# USB2Serial_CH340G_v1_0.net
KiCad netlist of a schematic drawn in EAGLE
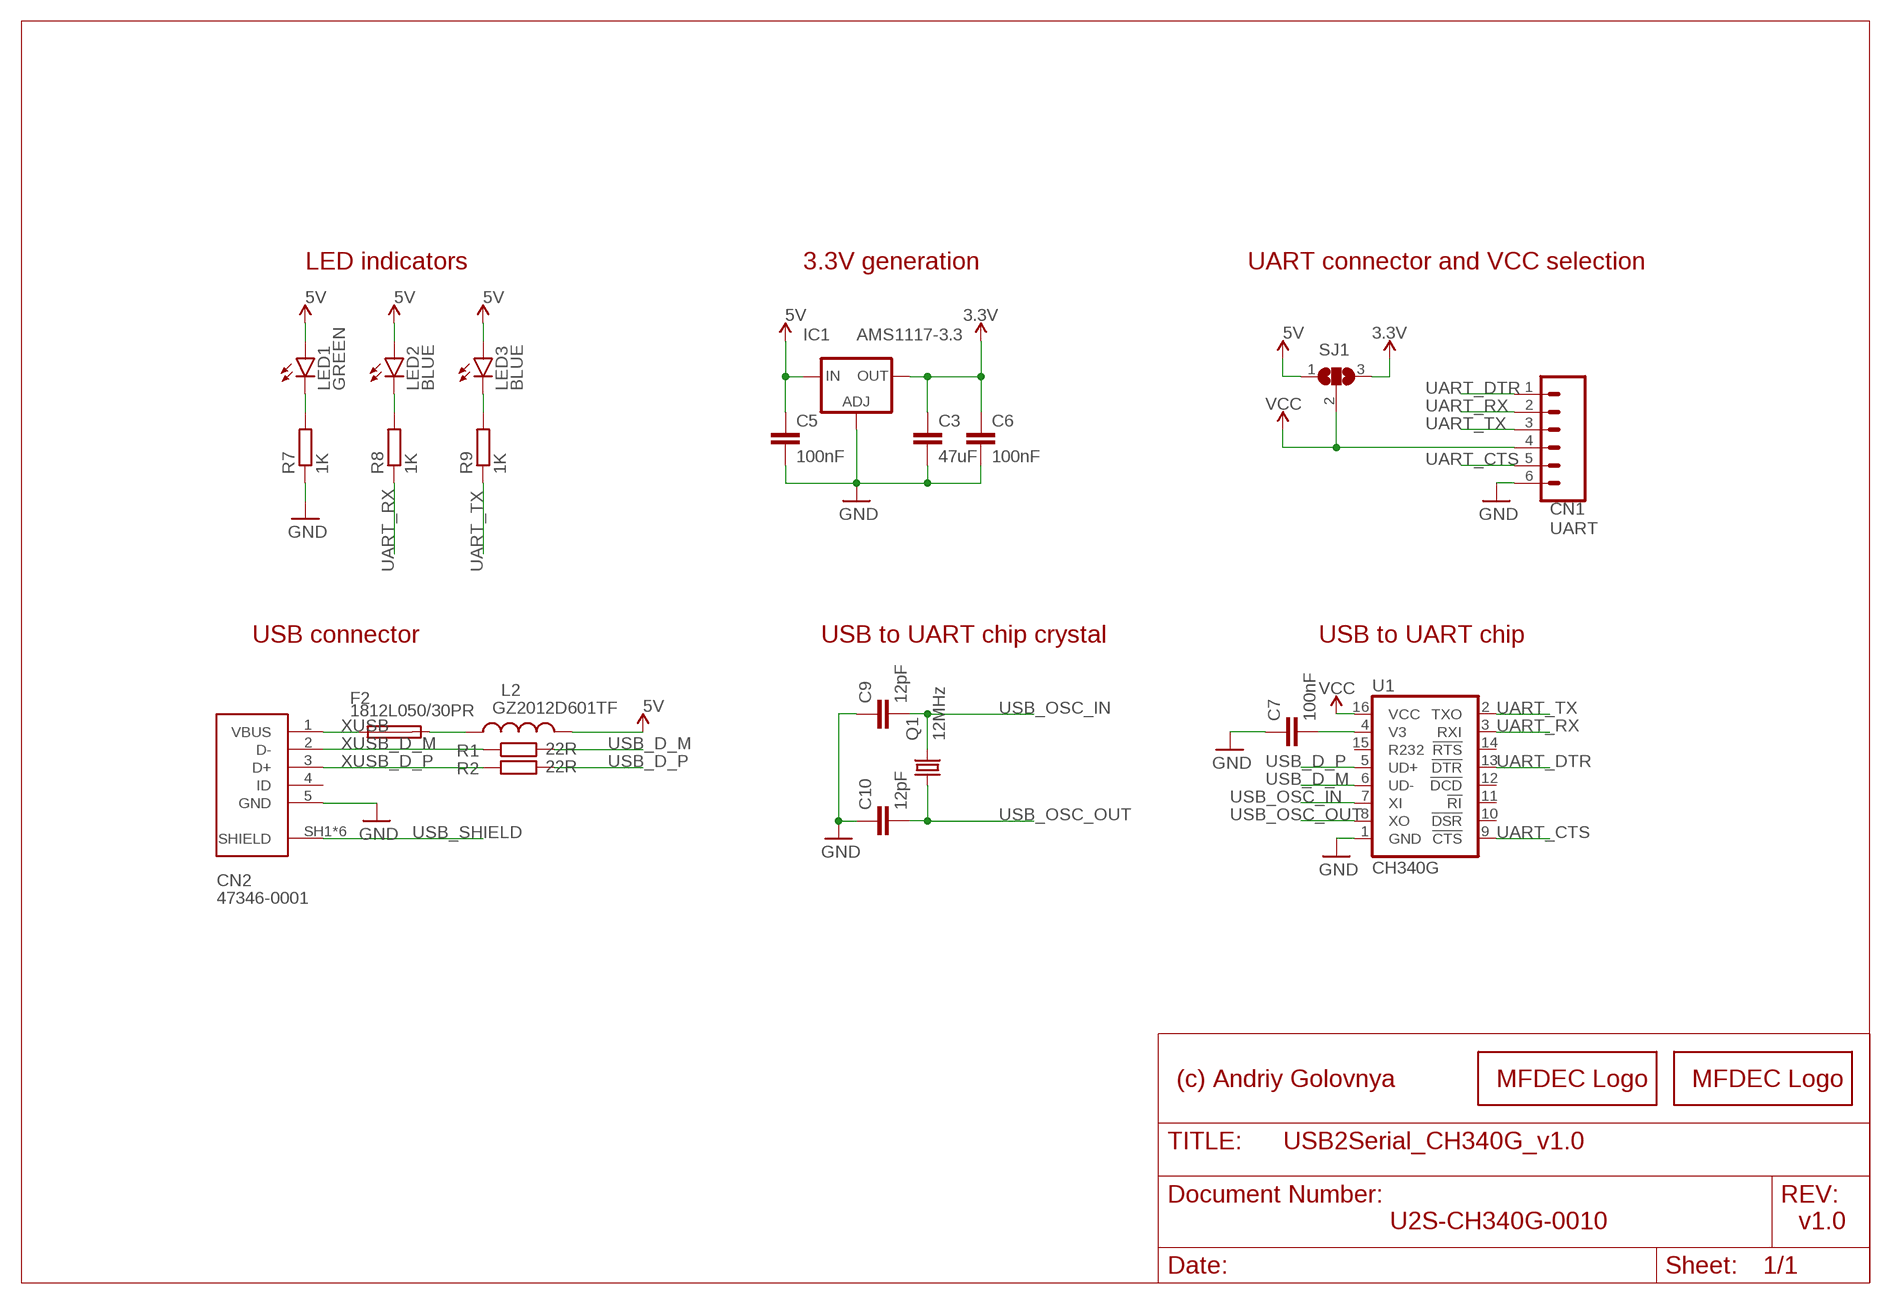
[diagram p0: schematic, sheet 1]

(export (version "E")
  (design (tool "Eeschema 10.0.6"))
  (components
    (comp (ref "C3")
      (value "47uF")
      (footprint "eagle-import:C0805")
      (libsource (lib "eagle-import") (part "C-EUC0805"))
    )
    (comp (ref "C5")
      (value "100nF")
      (footprint "eagle-import:C0402")
      (libsource (lib "eagle-import") (part "C-EUC0402"))
    )
    (comp (ref "C6")
      (value "100nF")
      (footprint "eagle-import:C0402")
      (libsource (lib "eagle-import") (part "C-EUC0402"))
    )
    (comp (ref "C7")
      (value "100nF")
      (footprint "eagle-import:C0402")
      (libsource (lib "eagle-import") (part "C-EUC0402"))
    )
    (comp (ref "C9")
      (value "12pF")
      (footprint "eagle-import:C0402")
      (libsource (lib "eagle-import") (part "C-EUC0402"))
    )
    (comp (ref "C10")
      (value "12pF")
      (footprint "eagle-import:C0402")
      (libsource (lib "eagle-import") (part "C-EUC0402"))
    )
    (comp (ref "CN1")
      (value "UART")
      (footprint "eagle-import:1X06_NO_SILK")
      (libsource (lib "eagle-import") (part "CONN_06NO_SILK_FEMALE_PTH"))
    )
    (comp (ref "CN2")
      (value "47346-0001")
      (footprint "eagle-import:MOLEX_47346-0001")
      (fields (field (name "MANUFACTURER") "Molex"))
      (libsource (lib "eagle-import") (part "47346-0001"))
    )
    (comp (ref "F2")
      (value "1812L050/30PR")
      (footprint "eagle-import:MF-SMDF050")
      (libsource (lib "eagle-import") (part "MF-SMDF050"))
    )
    (comp (ref "IC1")
      (value "AMS1117-3.3")
      (footprint "eagle-import:SOT223")
      (libsource (lib "eagle-import") (part "LD117A?S33TR"))
    )
    (comp (ref "L2")
      (value "GZ2012D601TF")
      (footprint "eagle-import:WE-CBA_0805(W=4)")
      (libsource (lib "eagle-import") (part "WE-CBA_0805_HC_782853102"))
    )
    (comp (ref "LED1")
      (value "GREEN")
      (footprint "eagle-import:SML0603")
      (libsource (lib "eagle-import") (part "LEDSML0603"))
    )
    (comp (ref "LED2")
      (value "BLUE")
      (footprint "eagle-import:SML0603")
      (libsource (lib "eagle-import") (part "LEDSML0603"))
    )
    (comp (ref "LED3")
      (value "BLUE")
      (footprint "eagle-import:SML0603")
      (libsource (lib "eagle-import") (part "LEDSML0603"))
    )
    (comp (ref "LOGO1")
      (value "MFDECLOGO_L_20MM")
      (footprint "eagle-import:MFDEC_L_20MM")
      (libsource (lib "eagle-import") (part "MFDECLOGO_L_20MM"))
    )
    (comp (ref "LOGO2")
      (value "MFDECLOGO_SQ_10MM")
      (footprint "eagle-import:MFDEC_SQ_10MM")
      (libsource (lib "eagle-import") (part "MFDECLOGO_SQ_10MM"))
    )
    (comp (ref "Q1")
      (value "12MHz")
      (footprint "eagle-import:3.2X2.5_KX-7")
      (libsource (lib "eagle-import") (part "KX-7"))
    )
    (comp (ref "R1")
      (value "22R")
      (footprint "eagle-import:R0402")
      (libsource (lib "eagle-import") (part "R-EU_R0402"))
    )
    (comp (ref "R2")
      (value "22R")
      (footprint "eagle-import:R0402")
      (libsource (lib "eagle-import") (part "R-EU_R0402"))
    )
    (comp (ref "R7")
      (value "1K")
      (footprint "eagle-import:R0402")
      (libsource (lib "eagle-import") (part "R-EU_R0402"))
    )
    (comp (ref "R8")
      (value "1K")
      (footprint "eagle-import:R0402")
      (libsource (lib "eagle-import") (part "R-EU_R0402"))
    )
    (comp (ref "R9")
      (value "1K")
      (footprint "eagle-import:R0402")
      (libsource (lib "eagle-import") (part "R-EU_R0402"))
    )
    (comp (ref "SJ1")
      (value "SJ2FI")
      (footprint "eagle-import:SJ_2FI")
      (libsource (lib "eagle-import") (part "SJ2FI"))
    )
    (comp (ref "U1")
      (value "CH340G")
      (footprint "eagle-import:SO016")
      (libsource (lib "eagle-import") (part "CH340GSMD"))
    )
  )
  (nets
    (net (code "1") (name "/UART_CTS") (class "Default")
      (node (ref "CN1") (pin "5") (pinfunction "5_5") (pintype "passive"))
      (node (ref "U1") (pin "9") (pinfunction "~{CTS}_9") (pintype "bidirectional"))
    )
    (net (code "2") (name "/UART_DTR") (class "Default")
      (node (ref "CN1") (pin "1") (pinfunction "1_1") (pintype "passive"))
      (node (ref "U1") (pin "13") (pinfunction "~{DTR}_13") (pintype "bidirectional"))
    )
    (net (code "3") (name "/UART_RX") (class "Default")
      (node (ref "CN1") (pin "2") (pinfunction "2_2") (pintype "passive"))
      (node (ref "R8") (pin "1") (pinfunction "1_1") (pintype "passive"))
      (node (ref "U1") (pin "3") (pinfunction "RXI_3") (pintype "bidirectional"))
    )
    (net (code "4") (name "/UART_TX") (class "Default")
      (node (ref "CN1") (pin "3") (pinfunction "3_3") (pintype "passive"))
      (node (ref "R9") (pin "1") (pinfunction "1_1") (pintype "passive"))
      (node (ref "U1") (pin "2") (pinfunction "TXO_2") (pintype "bidirectional"))
    )
    (net (code "5") (name "/USB_D_M") (class "Default")
      (node (ref "R1") (pin "2") (pinfunction "2_2") (pintype "passive"))
      (node (ref "U1") (pin "6") (pinfunction "UD-_6") (pintype "bidirectional"))
    )
    (net (code "6") (name "/USB_D_P") (class "Default")
      (node (ref "R2") (pin "2") (pinfunction "2_2") (pintype "passive"))
      (node (ref "U1") (pin "5") (pinfunction "UD+_5") (pintype "bidirectional"))
    )
    (net (code "7") (name "/USB_OSC_IN") (class "Default")
      (node (ref "C9") (pin "2") (pinfunction "2_2") (pintype "passive"))
      (node (ref "Q1") (pin "3") (pinfunction "2_3") (pintype "passive"))
      (node (ref "U1") (pin "7") (pinfunction "XI_7") (pintype "bidirectional"))
    )
    (net (code "8") (name "/USB_OSC_OUT") (class "Default")
      (node (ref "C10") (pin "2") (pinfunction "2_2") (pintype "passive"))
      (node (ref "Q1") (pin "1") (pinfunction "1_1") (pintype "passive"))
      (node (ref "U1") (pin "8") (pinfunction "XO_8") (pintype "bidirectional"))
    )
    (net (code "9") (name "/USB_SHIELD") (class "Default")
      (node (ref "CN2") (pin "SH1") (pinfunction "SHIELD_SH1") (pintype "passive"))
      (node (ref "CN2") (pin "SH2") (pinfunction "SHIELD_SH2") (pintype "passive"))
      (node (ref "CN2") (pin "SH3") (pinfunction "SHIELD_SH3") (pintype "passive"))
      (node (ref "CN2") (pin "SH4") (pinfunction "SHIELD_SH4") (pintype "passive"))
      (node (ref "CN2") (pin "SH5") (pinfunction "SHIELD_SH5") (pintype "passive"))
      (node (ref "CN2") (pin "SH6") (pinfunction "SHIELD_SH6") (pintype "passive"))
    )
    (net (code "10") (name "/XUSB") (class "Default")
      (node (ref "CN2") (pin "1") (pinfunction "VBUS_1") (pintype "power_in"))
      (node (ref "F2") (pin "1") (pinfunction "1_1") (pintype "passive"))
    )
    (net (code "11") (name "/XUSB_D_M") (class "Default")
      (node (ref "CN2") (pin "2") (pinfunction "D-_2") (pintype "bidirectional"))
      (node (ref "R1") (pin "1") (pinfunction "1_1") (pintype "passive"))
    )
    (net (code "12") (name "/XUSB_D_P") (class "Default")
      (node (ref "CN2") (pin "3") (pinfunction "D+_3") (pintype "bidirectional"))
      (node (ref "R2") (pin "1") (pinfunction "1_1") (pintype "passive"))
    )
    (net (code "13") (name "3.3V") (class "Default")
      (node (ref "C3") (pin "1") (pinfunction "1_1") (pintype "passive"))
      (node (ref "C6") (pin "1") (pinfunction "1_1") (pintype "passive"))
      (node (ref "IC1") (pin "4") (pinfunction "OUT_4") (pintype "passive"))
      (node (ref "SJ1") (pin "3") (pinfunction "3_3") (pintype "passive"))
    )
    (net (code "14") (name "5V") (class "Default")
      (node (ref "C5") (pin "1") (pinfunction "1_1") (pintype "passive"))
      (node (ref "IC1") (pin "3") (pinfunction "IN_3") (pintype "input"))
      (node (ref "L2") (pin "2") (pinfunction "2_2") (pintype "passive"))
      (node (ref "LED1") (pin "A") (pinfunction "A_A") (pintype "passive"))
      (node (ref "LED2") (pin "A") (pinfunction "A_A") (pintype "passive"))
      (node (ref "LED3") (pin "A") (pinfunction "A_A") (pintype "passive"))
      (node (ref "SJ1") (pin "1") (pinfunction "1_1") (pintype "passive"))
    )
    (net (code "15") (name "GND") (class "Default")
      (node (ref "C10") (pin "1") (pinfunction "1_1") (pintype "passive"))
      (node (ref "C3") (pin "2") (pinfunction "2_2") (pintype "passive"))
      (node (ref "C5") (pin "2") (pinfunction "2_2") (pintype "passive"))
      (node (ref "C6") (pin "2") (pinfunction "2_2") (pintype "passive"))
      (node (ref "C7") (pin "1") (pinfunction "1_1") (pintype "passive"))
      (node (ref "C9") (pin "1") (pinfunction "1_1") (pintype "passive"))
      (node (ref "CN1") (pin "6") (pinfunction "6_6") (pintype "passive"))
      (node (ref "CN2") (pin "5") (pinfunction "GND_5") (pintype "power_in"))
      (node (ref "IC1") (pin "1") (pinfunction "ADJ_1") (pintype "input"))
      (node (ref "R7") (pin "1") (pinfunction "1_1") (pintype "passive"))
      (node (ref "U1") (pin "1") (pinfunction "GND_1") (pintype "bidirectional"))
    )
    (net (code "16") (name "Net-(F2-Pad2)") (class "Default")
      (node (ref "F2") (pin "2") (pinfunction "2_2") (pintype "passive"))
      (node (ref "L2") (pin "1") (pinfunction "1_1") (pintype "passive"))
    )
    (net (code "17") (name "Net-(LED1-PadC)") (class "Default")
      (node (ref "LED1") (pin "C") (pinfunction "C_C") (pintype "passive"))
      (node (ref "R7") (pin "2") (pinfunction "2_2") (pintype "passive"))
    )
    (net (code "18") (name "Net-(LED2-PadC)") (class "Default")
      (node (ref "LED2") (pin "C") (pinfunction "C_C") (pintype "passive"))
      (node (ref "R8") (pin "2") (pinfunction "2_2") (pintype "passive"))
    )
    (net (code "19") (name "Net-(LED3-PadC)") (class "Default")
      (node (ref "LED3") (pin "C") (pinfunction "C_C") (pintype "passive"))
      (node (ref "R9") (pin "2") (pinfunction "2_2") (pintype "passive"))
    )
    (net (code "20") (name "Net-(U1-V3)") (class "Default")
      (node (ref "C7") (pin "2") (pinfunction "2_2") (pintype "passive"))
      (node (ref "U1") (pin "4") (pinfunction "V3_4") (pintype "bidirectional"))
    )
    (net (code "21") (name "VCC") (class "Default")
      (node (ref "CN1") (pin "4") (pinfunction "4_4") (pintype "passive"))
      (node (ref "SJ1") (pin "2") (pinfunction "2_2") (pintype "passive"))
      (node (ref "U1") (pin "16") (pinfunction "VCC_16") (pintype "bidirectional"))
    )
    (net (code "22") (name "unconnected-(CN2-ID-Pad4)") (class "Default")
      (node (ref "CN2") (pin "4") (pinfunction "ID_4") (pintype "passive"))
    )
    (net (code "23") (name "unconnected-(U1-R232-Pad15)") (class "Default")
      (node (ref "U1") (pin "15") (pinfunction "R232_15") (pintype "bidirectional"))
    )
    (net (code "24") (name "unconnected-(U1-~{DCD}-Pad12)") (class "Default")
      (node (ref "U1") (pin "12") (pinfunction "~{DCD}_12") (pintype "bidirectional"))
    )
    (net (code "25") (name "unconnected-(U1-~{DSR}-Pad10)") (class "Default")
      (node (ref "U1") (pin "10") (pinfunction "~{DSR}_10") (pintype "bidirectional"))
    )
    (net (code "26") (name "unconnected-(U1-~{RI}-Pad11)") (class "Default")
      (node (ref "U1") (pin "11") (pinfunction "~{RI}_11") (pintype "bidirectional"))
    )
    (net (code "27") (name "unconnected-(U1-~{RTS}-Pad14)") (class "Default")
      (node (ref "U1") (pin "14") (pinfunction "~{RTS}_14") (pintype "bidirectional"))
    )
  )
)
